# sensor-4.net
KiCad netlist of a schematic drawn in Altium Designer
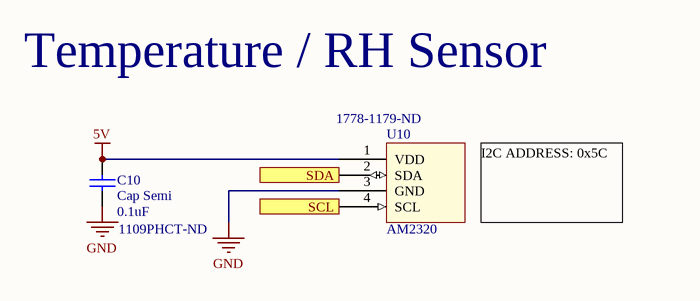
[diagram p0: sensor-4.SchDoc]

(export (version "E")
  (design (tool "Eeschema 10.0.6"))
  (components
    (comp (ref "C10")
      (value "Cap Semi")
      (footprint "A104K15X7RF5TAA")
      (description "Capacitor (Semiconductor SIM Model)")
      (fields
        (field (name "ALTIUM_VALUE") "0.1uF")
        (field (name "SUPPLIER PART NUMBER 1") "1109PHCT-ND")
        (field (name "MANUFACTURER") "Vishay BCcomponents")
        (field (name "MANUFACTURER PART NUMBER") "A104K15X7RF5TAA")
        (field (name "PUBLISHER") "Altium Limited")
      )
      (libsource (lib "Miscellaneous Devices") (part "Cap Semi"))
    )
    (comp (ref "U10")
      (value "AM2320")
      (footprint "AM2320")
      (description "Humidity Temperature Sensor 10 ~ 99% RH I²C ±3% RH 5s Through Hole")
      (fields
        (field (name "SUPPLIER PART NUMBER 1") "1778-1179-ND")
        (field (name "MANUFACTURER") "Pimoroni")
        (field (name "MANUFACTURER PART NUMBER") "COM1700")
      )
      (libsource (lib "Aosong") (part "AM2320"))
    )
  )
  (nets
    (net (code "1") (name "/SCL") (class "Default")
      (node (ref "U10") (pin "4") (pinfunction "SCL_4") (pintype "input"))
    )
    (net (code "2") (name "/SDA") (class "Default")
      (node (ref "U10") (pin "2") (pinfunction "SDA_2") (pintype "bidirectional"))
    )
    (net (code "3") (name "5V") (class "Default")
      (node (ref "C10") (pin "2") (pinfunction "2_2") (pintype "passive"))
      (node (ref "U10") (pin "1") (pinfunction "VDD_1") (pintype "power_in"))
    )
    (net (code "4") (name "GND") (class "Default")
      (node (ref "C10") (pin "1") (pinfunction "1_1") (pintype "passive"))
      (node (ref "U10") (pin "3") (pinfunction "GND_3") (pintype "power_in"))
    )
  )
)
